# V0p2_Main_PCB2.net
KiCad netlist of a schematic drawn in EAGLE
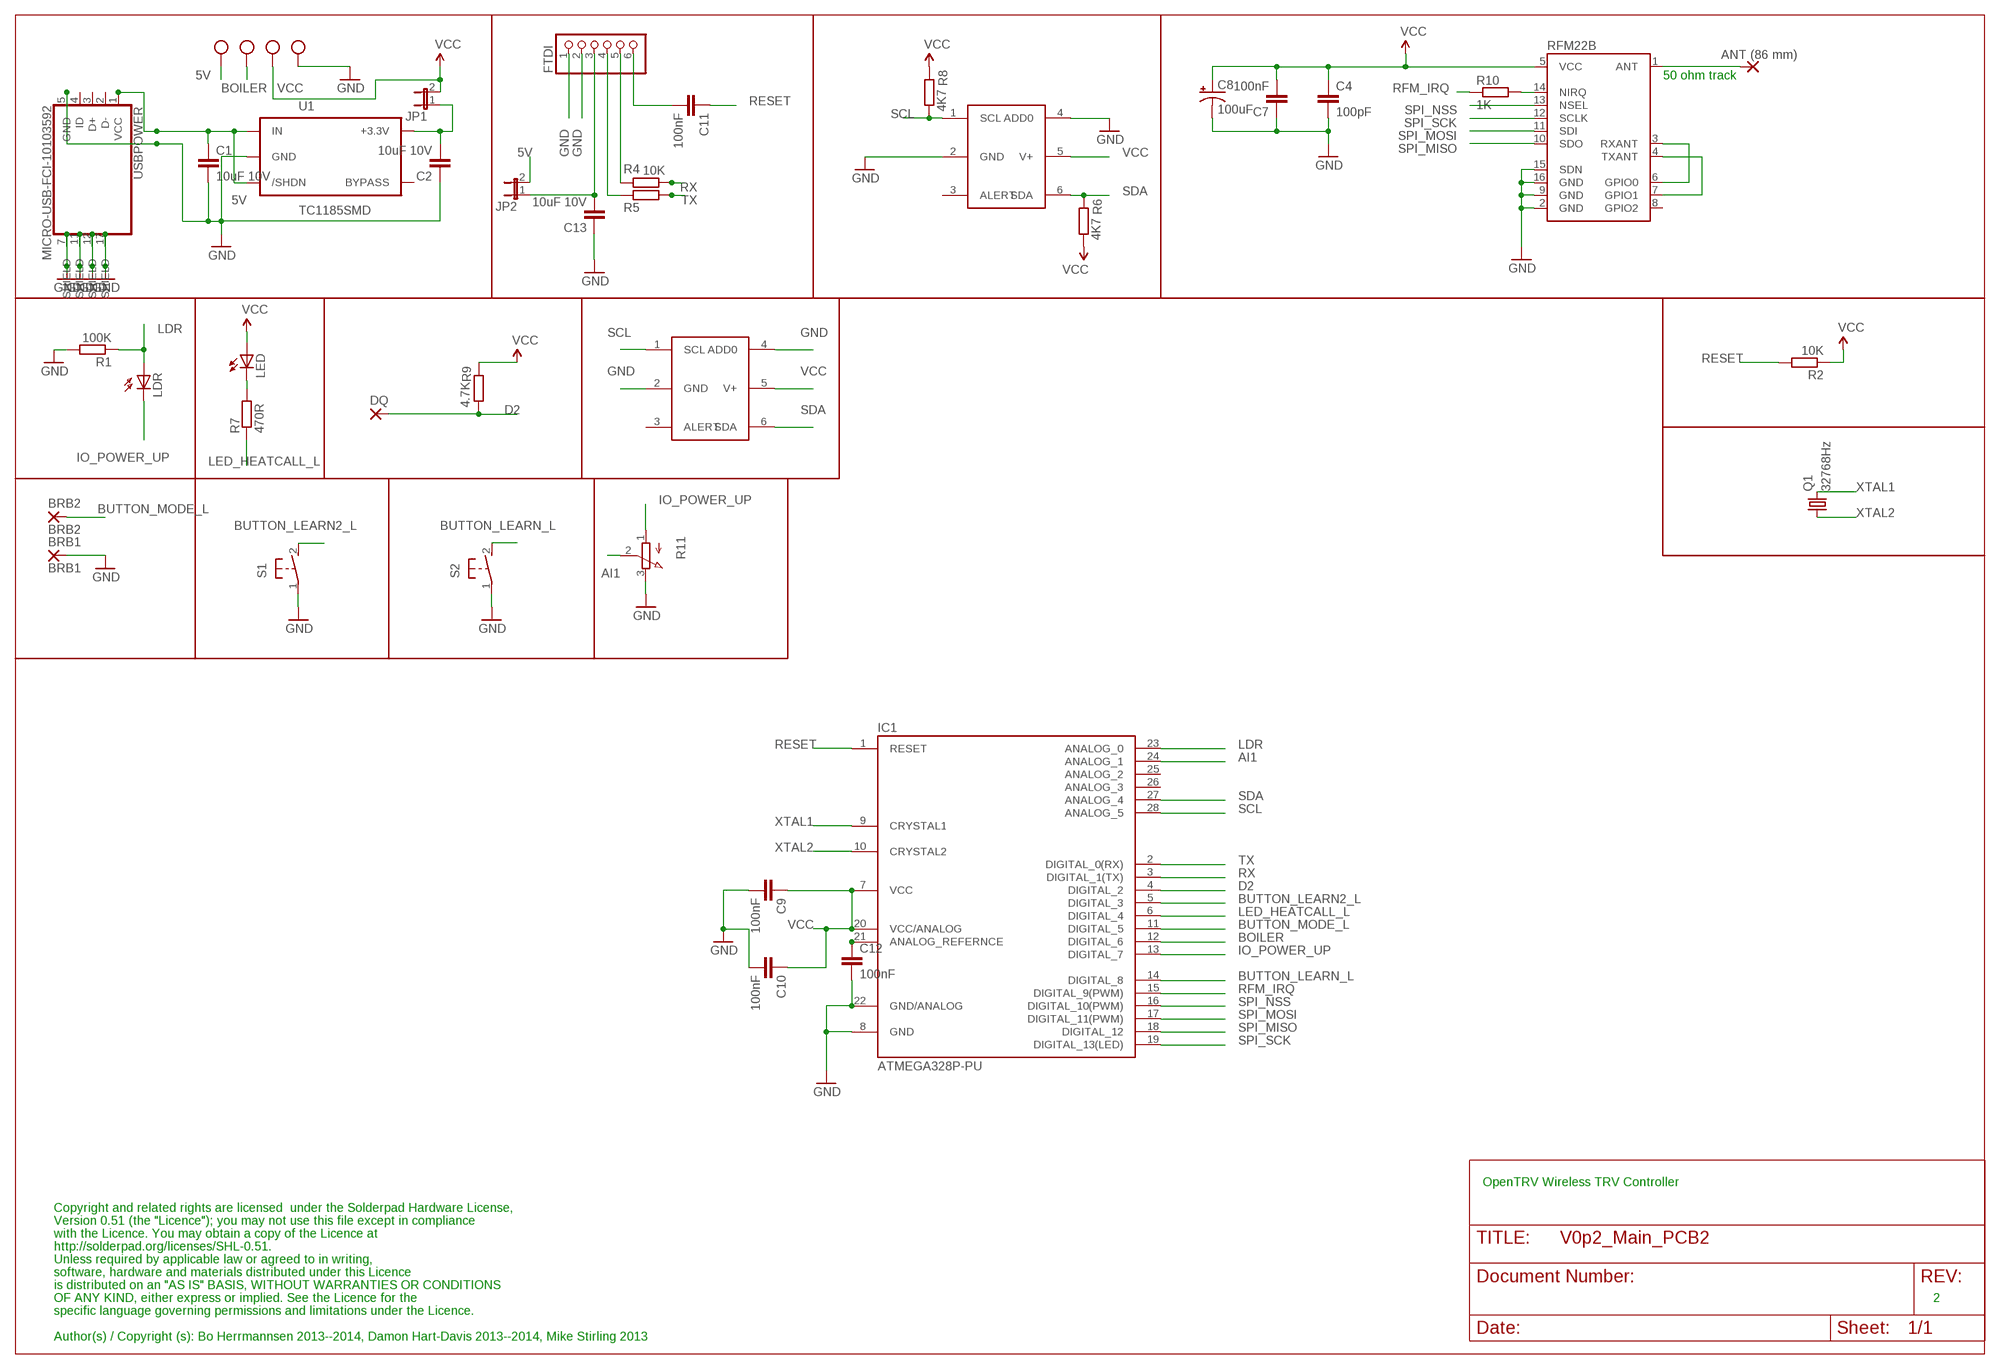
[diagram p0: schematic, sheet 1]

(export (version "E")
  (design (tool "Eeschema 10.0.6"))
  (components
    (comp (ref "ANT")
      (value "ANT (86 mm)")
      (footprint "eagle-import:2,15_1,0")
      (libsource (lib "eagle-import") (part "2,15/1,0"))
    )
    (comp (ref "BRB1")
      (value "BRB1")
      (footprint "eagle-import:2,15_1,0")
      (libsource (lib "eagle-import") (part "2,15/1,0"))
    )
    (comp (ref "BRB2")
      (value "BRB2")
      (footprint "eagle-import:2,15_1,0")
      (libsource (lib "eagle-import") (part "2,15/1,0"))
    )
    (comp (ref "C1")
      (value "10uF 10V")
      (footprint "eagle-import:0603-CAP")
      (libsource (lib "eagle-import") (part "CAP0603-CAP"))
    )
    (comp (ref "C2")
      (value "10uF 10V")
      (footprint "eagle-import:0603-CAP")
      (libsource (lib "eagle-import") (part "CAP0603-CAP"))
    )
    (comp (ref "C4")
      (value "100pF")
      (footprint "eagle-import:0603-CAP")
      (libsource (lib "eagle-import") (part "CAP0603-CAP"))
    )
    (comp (ref "C7")
      (value "100nF")
      (footprint "eagle-import:0603-CAP")
      (libsource (lib "eagle-import") (part "CAP0603-CAP"))
    )
    (comp (ref "C8")
      (value "100uF")
      (footprint "eagle-import:EIA3216")
      (libsource (lib "eagle-import") (part "CAP_POL1206"))
    )
    (comp (ref "C9")
      (value "100nF")
      (footprint "eagle-import:0603-CAP")
      (libsource (lib "eagle-import") (part "CAP0603-CAP"))
    )
    (comp (ref "C10")
      (value "100nF")
      (footprint "eagle-import:0603-CAP")
      (libsource (lib "eagle-import") (part "CAP0603-CAP"))
    )
    (comp (ref "C11")
      (value "100nF")
      (footprint "eagle-import:0603-CAP")
      (libsource (lib "eagle-import") (part "CAP0603-CAP"))
    )
    (comp (ref "C12")
      (value "100nF")
      (footprint "eagle-import:0603-CAP")
      (libsource (lib "eagle-import") (part "CAP0603-CAP"))
    )
    (comp (ref "C13")
      (value "10uF 10V")
      (footprint "eagle-import:0603-CAP")
      (libsource (lib "eagle-import") (part "CAP0603-CAP"))
    )
    (comp (ref "DQ")
      (value "2,15/1,0")
      (footprint "eagle-import:2,15_1,0")
      (libsource (lib "eagle-import") (part "2,15/1,0"))
    )
    (comp (ref "FTDI")
      (value "PINHD-1X6/90")
      (footprint "eagle-import:1X06_90")
      (libsource (lib "eagle-import") (part "PINHD-1X6/90"))
    )
    (comp (ref "IC1")
      (value "ATMEGA328P-PU")
      (footprint "eagle-import:DIL28-3")
      (libsource (lib "eagle-import") (part "ATMEGA8-PU"))
    )
    (comp (ref "JP1")
      (value "JP1E")
      (footprint "eagle-import:JP1")
      (libsource (lib "eagle-import") (part "JP1E"))
    )
    (comp (ref "JP2")
      (value "JP1E")
      (footprint "eagle-import:JP1")
      (libsource (lib "eagle-import") (part "JP1E"))
    )
    (comp (ref "LDR")
      (value "BPX65")
      (footprint "eagle-import:BPX65")
      (fields (field (name "MPN") "BPX65."))
      (libsource (lib "eagle-import") (part "BPX65"))
    )
    (comp (ref "LED")
      (value "LED3MM")
      (footprint "eagle-import:LED3MM")
      (libsource (lib "eagle-import") (part "LED3MM"))
    )
    (comp (ref "Q1")
      (value "32768Hz")
      (footprint "eagle-import:MC-306")
      (fields (field (name "MPN") "MC-306 60.0KHZ  100PPM ,12.5PF"))
      (libsource (lib "eagle-import") (part "MC-306"))
    )
    (comp (ref "R1")
      (value "100K")
      (footprint "eagle-import:R0603")
      (libsource (lib "eagle-import") (part "R-EU_R0603"))
    )
    (comp (ref "R2")
      (value "10K")
      (footprint "eagle-import:R0603")
      (libsource (lib "eagle-import") (part "R-EU_R0603"))
    )
    (comp (ref "R4")
      (value "10K")
      (footprint "eagle-import:R0603")
      (libsource (lib "eagle-import") (part "R-EU_R0603"))
    )
    (comp (ref "R5")
      (value "10K")
      (footprint "eagle-import:R0603")
      (libsource (lib "eagle-import") (part "R-EU_R0603"))
    )
    (comp (ref "R6")
      (value "4K7")
      (footprint "eagle-import:R0603")
      (libsource (lib "eagle-import") (part "R-EU_R0603"))
    )
    (comp (ref "R7")
      (value "470R")
      (footprint "eagle-import:R0603")
      (libsource (lib "eagle-import") (part "R-EU_R0603"))
    )
    (comp (ref "R8")
      (value "4K7")
      (footprint "eagle-import:R0603")
      (libsource (lib "eagle-import") (part "R-EU_R0603"))
    )
    (comp (ref "R9")
      (value "4.7K")
      (footprint "eagle-import:R0603")
      (libsource (lib "eagle-import") (part "R-EU_R0603"))
    )
    (comp (ref "R10")
      (value "1K")
      (footprint "eagle-import:R0603")
      (libsource (lib "eagle-import") (part "R-EU_R0603"))
    )
    (comp (ref "R11")
      (value "EVUE2A")
      (footprint "eagle-import:EVUE")
      (libsource (lib "eagle-import") (part "EVUE2A"))
    )
    (comp (ref "RFM22B")
      (value "RFM22SMD")
      (footprint "eagle-import:RFM22-XXX-S2")
      (libsource (lib "eagle-import") (part "RFM22SMD"))
    )
    (comp (ref "S1")
      (value "31-XX")
      (footprint "eagle-import:B3F-31XX")
      (libsource (lib "eagle-import") (part "31-XX"))
    )
    (comp (ref "S2")
      (value "31-XX")
      (footprint "eagle-import:B3F-31XX")
      (libsource (lib "eagle-import") (part "31-XX"))
    )
    (comp (ref "TMP1")
      (value "TMP1")
      (footprint "eagle-import:TMP112")
      (libsource (lib "eagle-import") (part "TMP112"))
    )
    (comp (ref "TMP2")
      (value "TMP2")
      (footprint "eagle-import:TMP112")
      (libsource (lib "eagle-import") (part "TMP112_2_TMP112"))
    )
    (comp (ref "U1")
      (value "TC1185SMD")
      (footprint "eagle-import:TC1185")
      (libsource (lib "eagle-import") (part "TC1185SMD"))
    )
    (comp (ref "USBPOWER")
      (value "MICRO-USB-FCI-10103592")
      (footprint "eagle-import:MICRO-USB-FCI-10103592")
      (libsource (lib "eagle-import") (part "MICRO-USB-FCI-10103592"))
    )
    (comp (ref "X1")
      (value "W237-102")
      (footprint "eagle-import:SCREWTERMINAL")
      (fields (field (name "MPN") "237-102"))
      (libsource (lib "eagle-import") (part "W237-102"))
    )
    (comp (ref "X2")
      (value "W237-102")
      (footprint "eagle-import:SCREWTERMINAL")
      (fields (field (name "MPN") "237-102"))
      (libsource (lib "eagle-import") (part "W237-102"))
    )
  )
  (nets
    (net (code "1") (name "/5V") (class "Default")
      (node (ref "C1") (pin "1") (pinfunction "1_1") (pintype "passive"))
      (node (ref "JP2") (pin "2") (pinfunction "2_2") (pintype "passive"))
      (node (ref "U1") (pin "1") (pinfunction "IN_1") (pintype "passive"))
      (node (ref "U1") (pin "3") (pinfunction "/SHDN_3") (pintype "passive"))
      (node (ref "USBPOWER") (pin "1") (pinfunction "VCC_1") (pintype "bidirectional"))
      (node (ref "X1") (pin "2") (pinfunction "KL_2") (pintype "passive"))
    )
    (net (code "2") (name "/AI1") (class "Default")
      (node (ref "IC1") (pin "24") (pinfunction "ANALOG_1_24") (pintype "bidirectional"))
      (node (ref "R11") (pin "2") (pinfunction "S_2") (pintype "passive"))
    )
    (net (code "3") (name "/BOILER") (class "Default")
      (node (ref "IC1") (pin "12") (pinfunction "DIGITAL_6_12") (pintype "bidirectional"))
      (node (ref "X1") (pin "1") (pinfunction "KL_1") (pintype "passive"))
    )
    (net (code "4") (name "/BUTTON_LEARN2_L") (class "Default")
      (node (ref "IC1") (pin "5") (pinfunction "DIGITAL_3_5") (pintype "bidirectional"))
      (node (ref "S1") (pin "2") (pinfunction "S_2") (pintype "passive"))
    )
    (net (code "5") (name "/BUTTON_LEARN_L") (class "Default")
      (node (ref "IC1") (pin "14") (pinfunction "DIGITAL_8_14") (pintype "bidirectional"))
      (node (ref "S2") (pin "2") (pinfunction "S_2") (pintype "passive"))
    )
    (net (code "6") (name "/BUTTON_MODE_L") (class "Default")
      (node (ref "BRB2") (pin "1") (pinfunction "P_1") (pintype "passive"))
      (node (ref "IC1") (pin "11") (pinfunction "DIGITAL_5_11") (pintype "bidirectional"))
    )
    (net (code "7") (name "/D2") (class "Default")
      (node (ref "DQ") (pin "1") (pinfunction "P_1") (pintype "passive"))
      (node (ref "IC1") (pin "4") (pinfunction "DIGITAL_2_4") (pintype "bidirectional"))
      (node (ref "R9") (pin "1") (pinfunction "1_1") (pintype "passive"))
    )
    (net (code "8") (name "/IO_POWER_UP") (class "Default")
      (node (ref "IC1") (pin "13") (pinfunction "DIGITAL_7_13") (pintype "bidirectional"))
      (node (ref "LDR") (pin "K") (pinfunction "C_K") (pintype "passive"))
      (node (ref "R11") (pin "1") (pinfunction "A_1") (pintype "passive"))
    )
    (net (code "9") (name "/LDR") (class "Default")
      (node (ref "IC1") (pin "23") (pinfunction "ANALOG_0_23") (pintype "bidirectional"))
      (node (ref "LDR") (pin "A") (pinfunction "A_A") (pintype "passive"))
      (node (ref "R1") (pin "1") (pinfunction "1_1") (pintype "passive"))
    )
    (net (code "10") (name "/LED_HEATCALL_L") (class "Default")
      (node (ref "IC1") (pin "6") (pinfunction "DIGITAL_4_6") (pintype "bidirectional"))
      (node (ref "R7") (pin "1") (pinfunction "1_1") (pintype "passive"))
    )
    (net (code "11") (name "/RESET") (class "Default")
      (node (ref "C11") (pin "1") (pinfunction "1_1") (pintype "passive"))
      (node (ref "IC1") (pin "1") (pinfunction "RESET_1") (pintype "bidirectional"))
      (node (ref "R2") (pin "2") (pinfunction "2_2") (pintype "passive"))
    )
    (net (code "12") (name "/RFM_IRQ") (class "Default")
      (node (ref "IC1") (pin "15") (pinfunction "DIGITAL_9(PWM)_15") (pintype "bidirectional"))
      (node (ref "R10") (pin "1") (pinfunction "1_1") (pintype "passive"))
    )
    (net (code "13") (name "/RX") (class "Default")
      (node (ref "IC1") (pin "3") (pinfunction "DIGITAL_1(TX)_3") (pintype "bidirectional"))
      (node (ref "R4") (pin "1") (pinfunction "1_1") (pintype "passive"))
    )
    (net (code "14") (name "/SCL") (class "Default")
      (node (ref "IC1") (pin "28") (pinfunction "ANALOG_5_28") (pintype "bidirectional"))
      (node (ref "R8") (pin "1") (pinfunction "1_1") (pintype "passive"))
      (node (ref "TMP1") (pin "1") (pinfunction "SCL_1") (pintype "bidirectional"))
      (node (ref "TMP2") (pin "1") (pinfunction "SCL_1") (pintype "bidirectional"))
    )
    (net (code "15") (name "/SDA") (class "Default")
      (node (ref "IC1") (pin "27") (pinfunction "ANALOG_4_27") (pintype "bidirectional"))
      (node (ref "R6") (pin "2") (pinfunction "2_2") (pintype "passive"))
      (node (ref "TMP1") (pin "6") (pinfunction "SDA_6") (pintype "bidirectional"))
      (node (ref "TMP2") (pin "6") (pinfunction "SDA_6") (pintype "bidirectional"))
    )
    (net (code "16") (name "/SPI_MISO") (class "Default")
      (node (ref "IC1") (pin "18") (pinfunction "DIGITAL_12_18") (pintype "bidirectional"))
      (node (ref "RFM22B") (pin "10") (pinfunction "SDO_10") (pintype "output"))
    )
    (net (code "17") (name "/SPI_MOSI") (class "Default")
      (node (ref "IC1") (pin "17") (pinfunction "DIGITAL_11(PWM)_17") (pintype "bidirectional"))
      (node (ref "RFM22B") (pin "11") (pinfunction "SDI_11") (pintype "input"))
    )
    (net (code "18") (name "/SPI_NSS") (class "Default")
      (node (ref "IC1") (pin "16") (pinfunction "DIGITAL_10(PWM)_16") (pintype "bidirectional"))
      (node (ref "RFM22B") (pin "13") (pinfunction "NSEL_13") (pintype "input"))
    )
    (net (code "19") (name "/SPI_SCK") (class "Default")
      (node (ref "IC1") (pin "19") (pinfunction "DIGITAL_13(LED)_19") (pintype "bidirectional"))
      (node (ref "RFM22B") (pin "12") (pinfunction "SCLK_12") (pintype "input"))
    )
    (net (code "20") (name "/TX") (class "Default")
      (node (ref "IC1") (pin "2") (pinfunction "DIGITAL_0(RX)_2") (pintype "bidirectional"))
      (node (ref "R5") (pin "1") (pinfunction "1_1") (pintype "passive"))
    )
    (net (code "21") (name "/XTAL1") (class "Default")
      (node (ref "IC1") (pin "9") (pinfunction "CRYSTAL1_9") (pintype "bidirectional"))
      (node (ref "Q1") (pin "4") (pinfunction "2_4") (pintype "passive"))
    )
    (net (code "22") (name "/XTAL2") (class "Default")
      (node (ref "IC1") (pin "10") (pinfunction "CRYSTAL2_10") (pintype "bidirectional"))
      (node (ref "Q1") (pin "1") (pinfunction "1_1") (pintype "passive"))
    )
    (net (code "23") (name "GND") (class "Default")
      (node (ref "BRB1") (pin "1") (pinfunction "P_1") (pintype "passive"))
      (node (ref "C1") (pin "2") (pinfunction "2_2") (pintype "passive"))
      (node (ref "C10") (pin "2") (pinfunction "2_2") (pintype "passive"))
      (node (ref "C12") (pin "2") (pinfunction "2_2") (pintype "passive"))
      (node (ref "C13") (pin "1") (pinfunction "1_1") (pintype "passive"))
      (node (ref "C2") (pin "1") (pinfunction "1_1") (pintype "passive"))
      (node (ref "C4") (pin "2") (pinfunction "2_2") (pintype "passive"))
      (node (ref "C7") (pin "1") (pinfunction "1_1") (pintype "passive"))
      (node (ref "C8") (pin "C") (pinfunction "-_C") (pintype "passive"))
      (node (ref "C9") (pin "2") (pinfunction "2_2") (pintype "passive"))
      (node (ref "FTDI") (pin "1") (pinfunction "1_1") (pintype "passive"))
      (node (ref "FTDI") (pin "2") (pinfunction "2_2") (pintype "passive"))
      (node (ref "IC1") (pin "22") (pinfunction "GND/ANALOG_22") (pintype "power_in"))
      (node (ref "IC1") (pin "8") (pinfunction "GND_8") (pintype "power_in"))
      (node (ref "R1") (pin "2") (pinfunction "2_2") (pintype "passive"))
      (node (ref "R11") (pin "3") (pinfunction "E_3") (pintype "passive"))
      (node (ref "RFM22B") (pin "15") (pinfunction "SDN_15") (pintype "input"))
      (node (ref "RFM22B") (pin "16") (pinfunction "GND_16") (pintype "power_in"))
      (node (ref "RFM22B") (pin "2") (pinfunction "GND_2") (pintype "power_in"))
      (node (ref "RFM22B") (pin "9") (pinfunction "GND_9") (pintype "power_in"))
      (node (ref "S1") (pin "1") (pinfunction "P_1") (pintype "passive"))
      (node (ref "S2") (pin "1") (pinfunction "P_1") (pintype "passive"))
      (node (ref "TMP1") (pin "2") (pinfunction "GND_2") (pintype "bidirectional"))
      (node (ref "TMP1") (pin "4") (pinfunction "ADD0_4") (pintype "bidirectional"))
      (node (ref "TMP2") (pin "2") (pinfunction "GND_2") (pintype "bidirectional"))
      (node (ref "TMP2") (pin "4") (pinfunction "ADD0_4") (pintype "bidirectional"))
      (node (ref "U1") (pin "2") (pinfunction "GND_2") (pintype "passive"))
      (node (ref "USBPOWER") (pin "11") (pinfunction "SHIELD_11") (pintype "bidirectional"))
      (node (ref "USBPOWER") (pin "12") (pinfunction "SHIELD_12") (pintype "bidirectional"))
      (node (ref "USBPOWER") (pin "17") (pinfunction "SHIELD_17") (pintype "bidirectional"))
      (node (ref "USBPOWER") (pin "5") (pinfunction "GND_5") (pintype "bidirectional"))
      (node (ref "USBPOWER") (pin "7") (pinfunction "SHIELD_7") (pintype "bidirectional"))
      (node (ref "X2") (pin "2") (pinfunction "KL_2") (pintype "passive"))
    )
    (net (code "24") (name "Net-(ANT-P)") (class "Default")
      (node (ref "ANT") (pin "1") (pinfunction "P_1") (pintype "passive"))
      (node (ref "RFM22B") (pin "1") (pinfunction "ANT_1") (pintype "bidirectional"))
    )
    (net (code "25") (name "Net-(C11-Pad2)") (class "Default")
      (node (ref "C11") (pin "2") (pinfunction "2_2") (pintype "passive"))
      (node (ref "FTDI") (pin "6") (pinfunction "6_6") (pintype "passive"))
    )
    (net (code "26") (name "Net-(C13-Pad2)") (class "Default")
      (node (ref "C13") (pin "2") (pinfunction "2_2") (pintype "passive"))
      (node (ref "FTDI") (pin "3") (pinfunction "3_3") (pintype "passive"))
      (node (ref "JP2") (pin "1") (pinfunction "1_1") (pintype "passive"))
    )
    (net (code "27") (name "Net-(FTDI-Pad4)") (class "Default")
      (node (ref "FTDI") (pin "4") (pinfunction "4_4") (pintype "passive"))
      (node (ref "R5") (pin "2") (pinfunction "2_2") (pintype "passive"))
    )
    (net (code "28") (name "Net-(FTDI-Pad5)") (class "Default")
      (node (ref "FTDI") (pin "5") (pinfunction "5_5") (pintype "passive"))
      (node (ref "R4") (pin "2") (pinfunction "2_2") (pintype "passive"))
    )
    (net (code "29") (name "Net-(IC1-ANALOG_REFERNCE)") (class "Default")
      (node (ref "C12") (pin "1") (pinfunction "1_1") (pintype "passive"))
      (node (ref "IC1") (pin "21") (pinfunction "ANALOG_REFERNCE_21") (pintype "passive"))
    )
    (net (code "30") (name "Net-(LED-C)") (class "Default")
      (node (ref "LED") (pin "K") (pinfunction "C_K") (pintype "passive"))
      (node (ref "R7") (pin "2") (pinfunction "2_2") (pintype "passive"))
    )
    (net (code "31") (name "Net-(RFM22B-GPIO0)") (class "Default")
      (node (ref "RFM22B") (pin "3") (pinfunction "RXANT_3") (pintype "input"))
      (node (ref "RFM22B") (pin "6") (pinfunction "GPIO0_6") (pintype "bidirectional"))
    )
    (net (code "32") (name "Net-(RFM22B-GPIO1)") (class "Default")
      (node (ref "RFM22B") (pin "4") (pinfunction "TXANT_4") (pintype "input"))
      (node (ref "RFM22B") (pin "7") (pinfunction "GPIO1_7") (pintype "bidirectional"))
    )
    (net (code "33") (name "Net-(RFM22B-NIRQ)") (class "Default")
      (node (ref "R10") (pin "2") (pinfunction "2_2") (pintype "passive"))
      (node (ref "RFM22B") (pin "14") (pinfunction "NIRQ_14") (pintype "output"))
    )
    (net (code "34") (name "Net-(U1-+3.3V)") (class "Default")
      (node (ref "C2") (pin "2") (pinfunction "2_2") (pintype "passive"))
      (node (ref "JP1") (pin "1") (pinfunction "1_1") (pintype "passive"))
      (node (ref "U1") (pin "5") (pinfunction "+3.3V_5") (pintype "power_in"))
    )
    (net (code "35") (name "VCC") (class "Default")
      (node (ref "C10") (pin "1") (pinfunction "1_1") (pintype "passive"))
      (node (ref "C4") (pin "1") (pinfunction "1_1") (pintype "passive"))
      (node (ref "C7") (pin "2") (pinfunction "2_2") (pintype "passive"))
      (node (ref "C8") (pin "A") (pinfunction "+_A") (pintype "passive"))
      (node (ref "C9") (pin "1") (pinfunction "1_1") (pintype "passive"))
      (node (ref "IC1") (pin "20") (pinfunction "VCC/ANALOG_20") (pintype "passive"))
      (node (ref "IC1") (pin "7") (pinfunction "VCC_7") (pintype "power_in"))
      (node (ref "JP1") (pin "2") (pinfunction "2_2") (pintype "passive"))
      (node (ref "LED") (pin "A") (pinfunction "A_A") (pintype "passive"))
      (node (ref "R2") (pin "1") (pinfunction "1_1") (pintype "passive"))
      (node (ref "R6") (pin "1") (pinfunction "1_1") (pintype "passive"))
      (node (ref "R8") (pin "2") (pinfunction "2_2") (pintype "passive"))
      (node (ref "R9") (pin "2") (pinfunction "2_2") (pintype "passive"))
      (node (ref "RFM22B") (pin "5") (pinfunction "VCC_5") (pintype "bidirectional"))
      (node (ref "TMP1") (pin "5") (pinfunction "V+_5") (pintype "bidirectional"))
      (node (ref "TMP2") (pin "5") (pinfunction "V+_5") (pintype "bidirectional"))
      (node (ref "X2") (pin "1") (pinfunction "KL_1") (pintype "passive"))
    )
    (net (code "36") (name "unconnected-(IC1-ANALOG_2-Pad25)") (class "Default")
      (node (ref "IC1") (pin "25") (pinfunction "ANALOG_2_25") (pintype "bidirectional"))
    )
    (net (code "37") (name "unconnected-(IC1-ANALOG_3-Pad26)") (class "Default")
      (node (ref "IC1") (pin "26") (pinfunction "ANALOG_3_26") (pintype "bidirectional"))
    )
    (net (code "38") (name "unconnected-(RFM22B-GPIO2-Pad8)") (class "Default")
      (node (ref "RFM22B") (pin "8") (pinfunction "GPIO2_8") (pintype "bidirectional"))
    )
    (net (code "39") (name "unconnected-(TMP1-ALERT-Pad3)") (class "Default")
      (node (ref "TMP1") (pin "3") (pinfunction "ALERT_3") (pintype "bidirectional"))
    )
    (net (code "40") (name "unconnected-(TMP2-ALERT-Pad3)") (class "Default")
      (node (ref "TMP2") (pin "3") (pinfunction "ALERT_3") (pintype "bidirectional"))
    )
    (net (code "41") (name "unconnected-(U1-BYPASS-Pad4)") (class "Default")
      (node (ref "U1") (pin "4") (pinfunction "BYPASS_4") (pintype "passive"))
    )
    (net (code "42") (name "unconnected-(USBPOWER-D+-Pad3)") (class "Default")
      (node (ref "USBPOWER") (pin "3") (pinfunction "D+_3") (pintype "bidirectional"))
    )
    (net (code "43") (name "unconnected-(USBPOWER-D--Pad2)") (class "Default")
      (node (ref "USBPOWER") (pin "2") (pinfunction "D-_2") (pintype "bidirectional"))
    )
    (net (code "44") (name "unconnected-(USBPOWER-ID-Pad4)") (class "Default")
      (node (ref "USBPOWER") (pin "4") (pinfunction "ID_4") (pintype "bidirectional"))
    )
  )
)
